# 18650BatteryCapacitanceR1.net
KiCad netlist of a schematic drawn in EAGLE
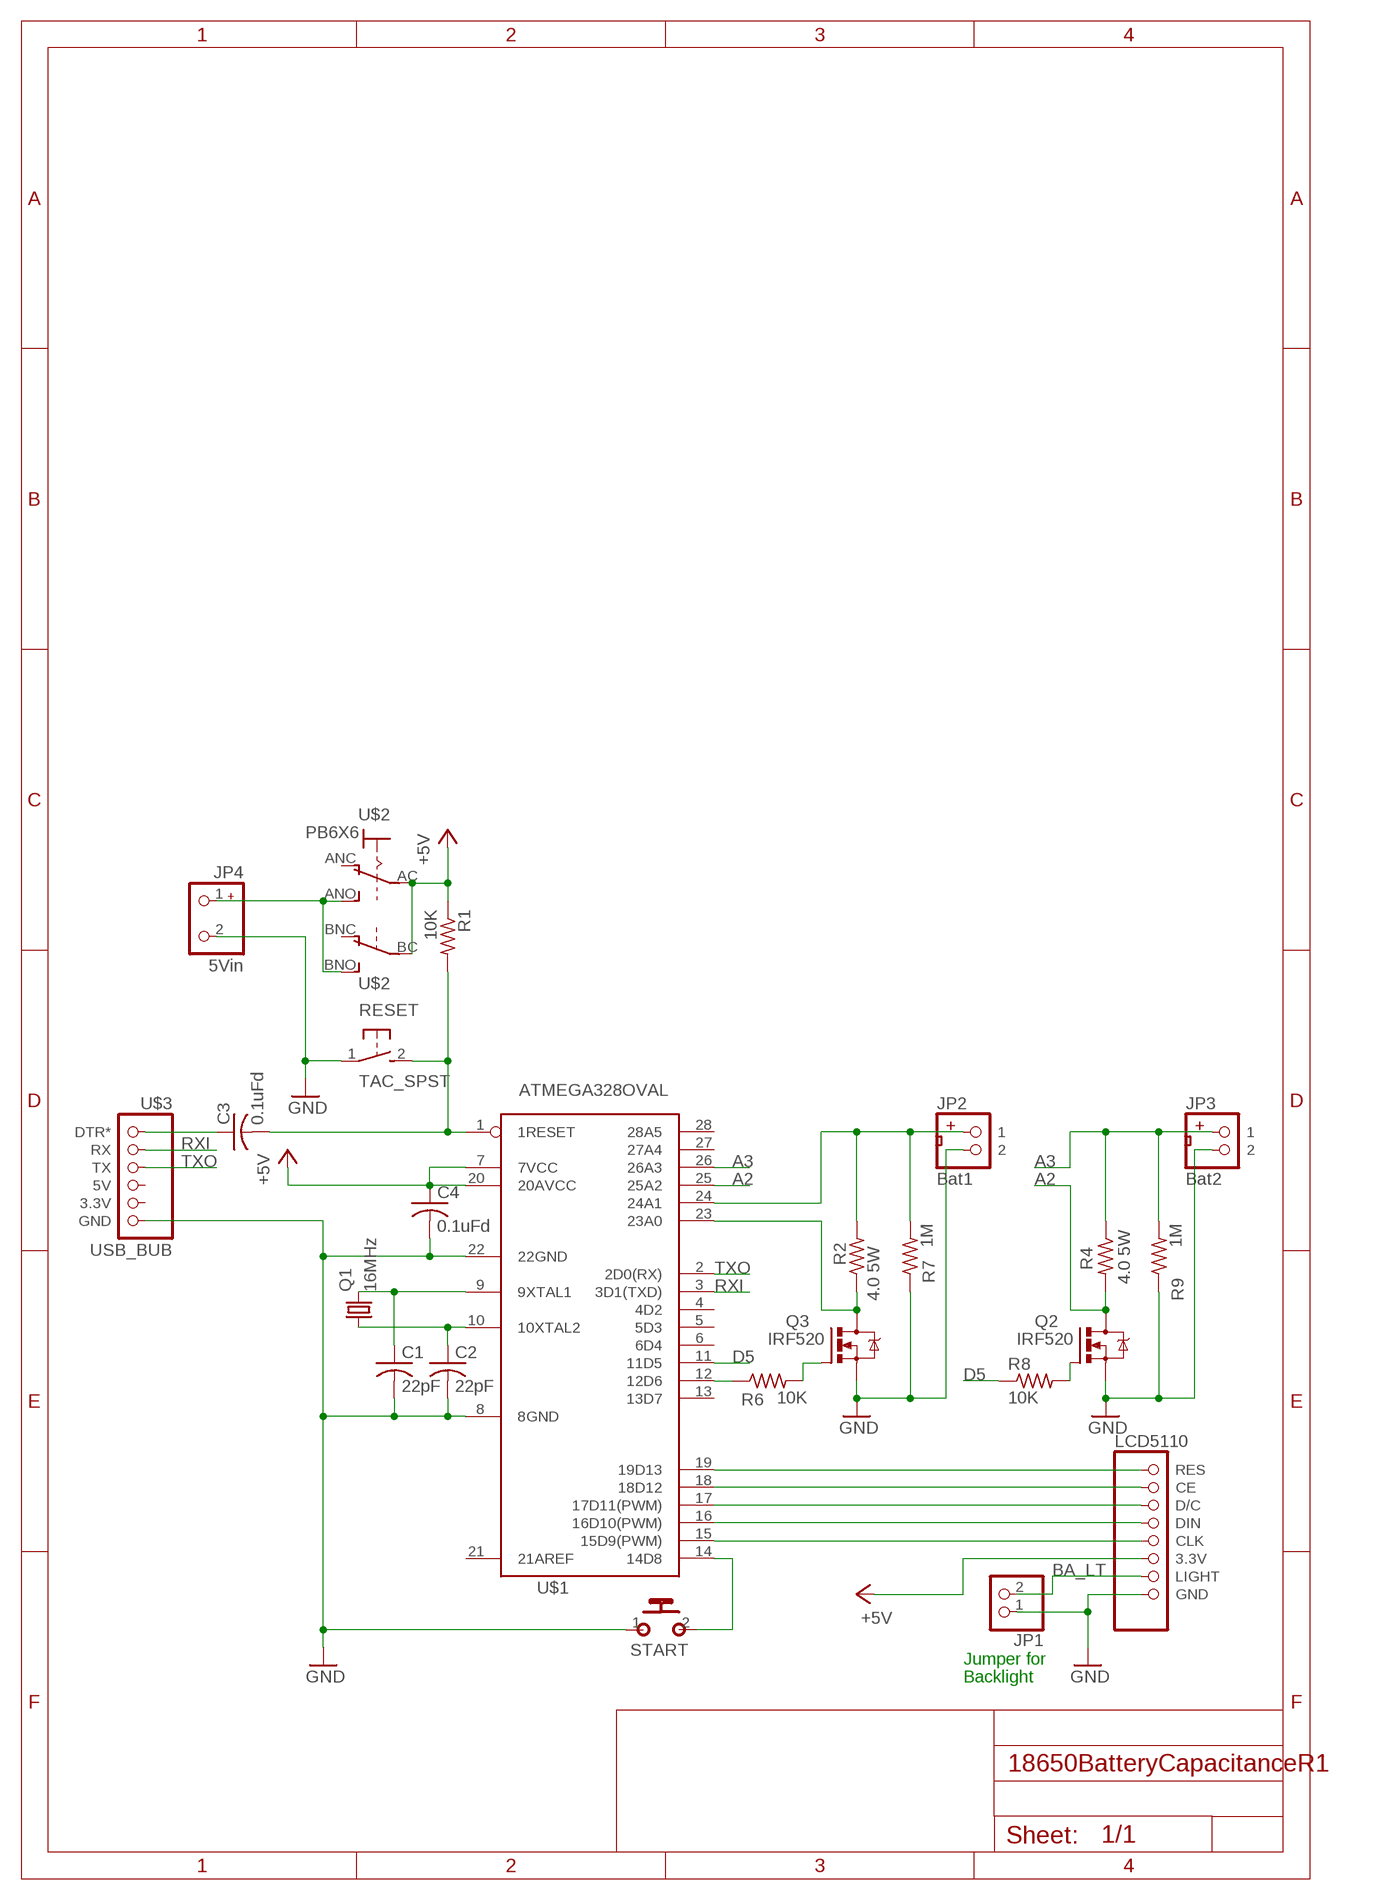
[diagram p0: schematic, sheet 1]

(export (version "E")
  (design (tool "Eeschema 10.0.6"))
  (components
    (comp (ref "C1")
      (value "22pF")
      (footprint "eagle-import:C025-025X050")
      (libsource (lib "eagle-import") (part "C-US025-025X050"))
    )
    (comp (ref "C2")
      (value "22pF")
      (footprint "eagle-import:C025-025X050")
      (libsource (lib "eagle-import") (part "C-US025-025X050"))
    )
    (comp (ref "C3")
      (value "0.1uFd")
      (footprint "eagle-import:C075-032X103")
      (libsource (lib "eagle-import") (part "C-US075-032X103"))
    )
    (comp (ref "C4")
      (value "0.1uFd")
      (footprint "eagle-import:C025-025X050")
      (libsource (lib "eagle-import") (part "C-US025-025X050"))
    )
    (comp (ref "JP1")
      (value "PINHD-1X2")
      (footprint "eagle-import:1X02")
      (libsource (lib "eagle-import") (part "PINHD-1X2"))
    )
    (comp (ref "JP2")
      (value "Bat1")
      (footprint "eagle-import:JST2.0")
      (libsource (lib "eagle-import") (part "JST2.0"))
    )
    (comp (ref "JP3")
      (value "Bat2")
      (footprint "eagle-import:JST2.0")
      (libsource (lib "eagle-import") (part "JST2.0"))
    )
    (comp (ref "JP4")
      (value "5Vin")
      (footprint "eagle-import:KF301")
      (libsource (lib "eagle-import") (part "KF301"))
    )
    (comp (ref "LCD5110")
      (value "LCD5110_1TOP")
      (footprint "eagle-import:LCD5110T1")
      (libsource (lib "eagle-import") (part "LCD5110_1TOP"))
    )
    (comp (ref "Q1")
      (value "16MHz")
      (footprint "eagle-import:HC49_S")
      (libsource (lib "eagle-import") (part "CRYSTALHC49S"))
    )
    (comp (ref "Q2")
      (value "IRF520")
      (footprint "eagle-import:TO220BV")
      (libsource (lib "eagle-import") (part "IRF520"))
    )
    (comp (ref "Q3")
      (value "IRF520")
      (footprint "eagle-import:TO220BV")
      (libsource (lib "eagle-import") (part "IRF520"))
    )
    (comp (ref "R1")
      (value "10K")
      (footprint "eagle-import:0207_7")
      (libsource (lib "eagle-import") (part "R-US_0207/7"))
    )
    (comp (ref "R2")
      (value "4.0 5W")
      (footprint "eagle-import:0922_22")
      (libsource (lib "eagle-import") (part "resistor_R-US_0922/22"))
    )
    (comp (ref "R4")
      (value "4.0 5W")
      (footprint "eagle-import:0922_22")
      (libsource (lib "eagle-import") (part "resistor_R-US_0922/22"))
    )
    (comp (ref "R6")
      (value "10K")
      (footprint "eagle-import:0207_7")
      (libsource (lib "eagle-import") (part "R-US_0207/7"))
    )
    (comp (ref "R7")
      (value "1M")
      (footprint "eagle-import:0207_2V")
      (libsource (lib "eagle-import") (part "R-US_0207/2V"))
    )
    (comp (ref "R8")
      (value "10K")
      (footprint "eagle-import:0207_7")
      (libsource (lib "eagle-import") (part "R-US_0207/7"))
    )
    (comp (ref "R9")
      (value "1M")
      (footprint "eagle-import:0207_2V")
      (libsource (lib "eagle-import") (part "R-US_0207/2V"))
    )
    (comp (ref "RESET")
      (value "TAC_SPST")
      (footprint "eagle-import:TACTILE-SPST")
      (libsource (lib "eagle-import") (part "TAC_SPST"))
    )
    (comp (ref "START")
      (value "MOMENTARY")
      (footprint "eagle-import:SPST")
      (libsource (lib "eagle-import") (part "MOMENTARY"))
    )
    (comp (ref "U$1")
      (value "ATMEGA328OVAL")
      (footprint "eagle-import:DIL28-3")
      (libsource (lib "eagle-import") (part "ATMEGA328OVAL"))
    )
    (comp (ref "U$2")
      (value "PB6X6")
      (footprint "eagle-import:PB6X6")
      (libsource (lib "eagle-import") (part "PB6X6"))
    )
    (comp (ref "U$3")
      (value "USB_BUB")
      (footprint "eagle-import:USB_BUB")
      (libsource (lib "eagle-import") (part "USB_BUB"))
    )
  )
  (nets
    (net (code "1") (name "+5V") (class "Default")
      (node (ref "C4") (pin "1") (pinfunction "1_1") (pintype "passive"))
      (node (ref "LCD5110") (pin "3.3V") (pinfunction "3.3V_3.3V") (pintype "passive"))
      (node (ref "R1") (pin "1") (pinfunction "1_1") (pintype "passive"))
      (node (ref "U$1") (pin "20") (pinfunction "20AVCC_20") (pintype "bidirectional"))
      (node (ref "U$1") (pin "7") (pinfunction "7VCC_7") (pintype "bidirectional"))
      (node (ref "U$2") (pin "AC") (pinfunction "P_AC") (pintype "passive"))
      (node (ref "U$2") (pin "BC") (pinfunction "P_BC") (pintype "passive"))
    )
    (net (code "2") (name "/A2") (class "Default")
      (node (ref "Q2") (pin "D") (pinfunction "D_D") (pintype "passive"))
      (node (ref "R4") (pin "2") (pinfunction "2_2") (pintype "passive"))
      (node (ref "U$1") (pin "25") (pinfunction "25A2_25") (pintype "bidirectional"))
    )
    (net (code "3") (name "/A3") (class "Default")
      (node (ref "JP3") (pin "1") (pinfunction "1_1") (pintype "passive"))
      (node (ref "R4") (pin "1") (pinfunction "1_1") (pintype "passive"))
      (node (ref "R9") (pin "2") (pinfunction "2_2") (pintype "passive"))
      (node (ref "U$1") (pin "26") (pinfunction "26A3_26") (pintype "bidirectional"))
    )
    (net (code "4") (name "/BA_LT") (class "Default")
      (node (ref "JP1") (pin "2") (pinfunction "2_2") (pintype "passive"))
      (node (ref "LCD5110") (pin "LIGHT") (pinfunction "LIGHT_LIGHT") (pintype "passive"))
    )
    (net (code "5") (name "/D5") (class "Default")
      (node (ref "R8") (pin "1") (pinfunction "1_1") (pintype "passive"))
      (node (ref "U$1") (pin "11") (pinfunction "11D5_11") (pintype "bidirectional"))
    )
    (net (code "6") (name "/RXI") (class "Default")
      (node (ref "U$1") (pin "3") (pinfunction "3D1(TXD)_3") (pintype "bidirectional"))
      (node (ref "U$3") (pin "RX") (pinfunction "RX_RX") (pintype "passive"))
    )
    (net (code "7") (name "/TXO") (class "Default")
      (node (ref "U$1") (pin "2") (pinfunction "2D0(RX)_2") (pintype "bidirectional"))
      (node (ref "U$3") (pin "TX") (pinfunction "TX_TX") (pintype "passive"))
    )
    (net (code "8") (name "GND") (class "Default")
      (node (ref "C1") (pin "2") (pinfunction "2_2") (pintype "passive"))
      (node (ref "C2") (pin "2") (pinfunction "2_2") (pintype "passive"))
      (node (ref "C4") (pin "2") (pinfunction "2_2") (pintype "passive"))
      (node (ref "JP1") (pin "1") (pinfunction "1_1") (pintype "passive"))
      (node (ref "JP2") (pin "2") (pinfunction "2_2") (pintype "passive"))
      (node (ref "JP3") (pin "2") (pinfunction "2_2") (pintype "passive"))
      (node (ref "JP4") (pin "2") (pinfunction "2_2") (pintype "passive"))
      (node (ref "LCD5110") (pin "GND") (pinfunction "GND_GND") (pintype "passive"))
      (node (ref "Q2") (pin "S") (pinfunction "S_S") (pintype "passive"))
      (node (ref "Q3") (pin "S") (pinfunction "S_S") (pintype "passive"))
      (node (ref "R7") (pin "1") (pinfunction "1_1") (pintype "passive"))
      (node (ref "R9") (pin "1") (pinfunction "1_1") (pintype "passive"))
      (node (ref "RESET") (pin "1") (pinfunction "1_1") (pintype "passive"))
      (node (ref "START") (pin "1") (pinfunction "P_1") (pintype "passive"))
      (node (ref "U$1") (pin "22") (pinfunction "22GND_22") (pintype "bidirectional"))
      (node (ref "U$1") (pin "8") (pinfunction "8GND_8") (pintype "bidirectional"))
      (node (ref "U$3") (pin "GND") (pinfunction "GND_GND") (pintype "passive"))
    )
    (net (code "9") (name "Net-(C3-Pad1)") (class "Default")
      (node (ref "C3") (pin "1") (pinfunction "1_1") (pintype "passive"))
      (node (ref "U$3") (pin "DTR*") (pinfunction "DTR*_DTR*") (pintype "passive"))
    )
    (net (code "10") (name "Net-(Q2-PadG)") (class "Default")
      (node (ref "Q2") (pin "G") (pinfunction "G_G") (pintype "passive"))
      (node (ref "R8") (pin "2") (pinfunction "2_2") (pintype "passive"))
    )
    (net (code "11") (name "Net-(Q3-PadG)") (class "Default")
      (node (ref "Q3") (pin "G") (pinfunction "G_G") (pintype "passive"))
      (node (ref "R6") (pin "2") (pinfunction "2_2") (pintype "passive"))
    )
    (net (code "12") (name "Net-(START-S)") (class "Default")
      (node (ref "START") (pin "2") (pinfunction "S_2") (pintype "passive"))
      (node (ref "U$1") (pin "14") (pinfunction "14D8_14") (pintype "bidirectional"))
    )
    (net (code "13") (name "Net-(U$1-1RESET)") (class "Default")
      (node (ref "C3") (pin "2") (pinfunction "2_2") (pintype "passive"))
      (node (ref "R1") (pin "2") (pinfunction "2_2") (pintype "passive"))
      (node (ref "RESET") (pin "2") (pinfunction "2_2") (pintype "passive"))
      (node (ref "U$1") (pin "1") (pinfunction "1RESET_1") (pintype "bidirectional"))
    )
    (net (code "14") (name "Net-(U$1-9XTAL1)") (class "Default")
      (node (ref "C1") (pin "1") (pinfunction "1_1") (pintype "passive"))
      (node (ref "Q1") (pin "2") (pinfunction "2_2") (pintype "passive"))
      (node (ref "U$1") (pin "9") (pinfunction "9XTAL1_9") (pintype "bidirectional"))
    )
    (net (code "15") (name "Net-(U$1-10XTAL2)") (class "Default")
      (node (ref "C2") (pin "1") (pinfunction "1_1") (pintype "passive"))
      (node (ref "Q1") (pin "1") (pinfunction "1_1") (pintype "passive"))
      (node (ref "U$1") (pin "10") (pinfunction "10XTAL2_10") (pintype "bidirectional"))
    )
    (net (code "16") (name "Net-(U$1-12D6)") (class "Default")
      (node (ref "R6") (pin "1") (pinfunction "1_1") (pintype "passive"))
      (node (ref "U$1") (pin "12") (pinfunction "12D6_12") (pintype "bidirectional"))
    )
    (net (code "17") (name "Net-(U$1-15D9(PWM))") (class "Default")
      (node (ref "LCD5110") (pin "CLK") (pinfunction "CLK_CLK") (pintype "passive"))
      (node (ref "U$1") (pin "15") (pinfunction "15D9(PWM)_15") (pintype "bidirectional"))
    )
    (net (code "18") (name "Net-(U$1-16D10(PWM))") (class "Default")
      (node (ref "LCD5110") (pin "DIN") (pinfunction "DIN_DIN") (pintype "passive"))
      (node (ref "U$1") (pin "16") (pinfunction "16D10(PWM)_16") (pintype "bidirectional"))
    )
    (net (code "19") (name "Net-(U$1-17D11(PWM))") (class "Default")
      (node (ref "LCD5110") (pin "D/C") (pinfunction "D/C_D/C") (pintype "passive"))
      (node (ref "U$1") (pin "17") (pinfunction "17D11(PWM)_17") (pintype "bidirectional"))
    )
    (net (code "20") (name "Net-(U$1-18D12)") (class "Default")
      (node (ref "LCD5110") (pin "CE") (pinfunction "CE_CE") (pintype "passive"))
      (node (ref "U$1") (pin "18") (pinfunction "18D12_18") (pintype "bidirectional"))
    )
    (net (code "21") (name "Net-(U$1-19D13)") (class "Default")
      (node (ref "LCD5110") (pin "RES") (pinfunction "RES_RES") (pintype "passive"))
      (node (ref "U$1") (pin "19") (pinfunction "19D13_19") (pintype "bidirectional"))
    )
    (net (code "22") (name "Net-(U$1-23A0)") (class "Default")
      (node (ref "Q3") (pin "D") (pinfunction "D_D") (pintype "passive"))
      (node (ref "R2") (pin "1") (pinfunction "1_1") (pintype "passive"))
      (node (ref "U$1") (pin "23") (pinfunction "23A0_23") (pintype "bidirectional"))
    )
    (net (code "23") (name "Net-(U$1-24A1)") (class "Default")
      (node (ref "JP2") (pin "1") (pinfunction "1_1") (pintype "passive"))
      (node (ref "R2") (pin "2") (pinfunction "2_2") (pintype "passive"))
      (node (ref "R7") (pin "2") (pinfunction "2_2") (pintype "passive"))
      (node (ref "U$1") (pin "24") (pinfunction "24A1_24") (pintype "bidirectional"))
    )
    (net (code "24") (name "Net-(U$2A-S)") (class "Default")
      (node (ref "JP4") (pin "1") (pinfunction "1_1") (pintype "passive"))
      (node (ref "U$2") (pin "ANO") (pinfunction "S_ANO") (pintype "passive"))
      (node (ref "U$2") (pin "BNO") (pinfunction "S_BNO") (pintype "passive"))
    )
    (net (code "25") (name "unconnected-(U$1-4D2-Pad4)") (class "Default")
      (node (ref "U$1") (pin "4") (pinfunction "4D2_4") (pintype "bidirectional"))
    )
    (net (code "26") (name "unconnected-(U$1-5D3-Pad5)") (class "Default")
      (node (ref "U$1") (pin "5") (pinfunction "5D3_5") (pintype "bidirectional"))
    )
    (net (code "27") (name "unconnected-(U$1-6D4-Pad6)") (class "Default")
      (node (ref "U$1") (pin "6") (pinfunction "6D4_6") (pintype "bidirectional"))
    )
    (net (code "28") (name "unconnected-(U$1-13D7-Pad13)") (class "Default")
      (node (ref "U$1") (pin "13") (pinfunction "13D7_13") (pintype "bidirectional"))
    )
    (net (code "29") (name "unconnected-(U$1-21AREF-Pad21)") (class "Default")
      (node (ref "U$1") (pin "21") (pinfunction "21AREF_21") (pintype "bidirectional"))
    )
    (net (code "30") (name "unconnected-(U$1-27A4-Pad27)") (class "Default")
      (node (ref "U$1") (pin "27") (pinfunction "27A4_27") (pintype "bidirectional"))
    )
    (net (code "31") (name "unconnected-(U$1-28A5-Pad28)") (class "Default")
      (node (ref "U$1") (pin "28") (pinfunction "28A5_28") (pintype "bidirectional"))
    )
    (net (code "32") (name "unconnected-(U$2A-O-PadANC)") (class "Default")
      (node (ref "U$2") (pin "ANC") (pinfunction "O_ANC") (pintype "passive"))
    )
    (net (code "33") (name "unconnected-(U$2B-O-PadBNC)") (class "Default")
      (node (ref "U$2") (pin "BNC") (pinfunction "O_BNC") (pintype "passive"))
    )
    (net (code "34") (name "unconnected-(U$3-Pad3.3V)") (class "Default")
      (node (ref "U$3") (pin "3.3V") (pinfunction "3.3V_3.3V") (pintype "passive"))
    )
    (net (code "35") (name "unconnected-(U$3-Pad5V)") (class "Default")
      (node (ref "U$3") (pin "5V") (pinfunction "5V_5V") (pintype "passive"))
    )
  )
)
